# IFM_DuberFilter_ThroughHole_PCB_REV1.net
KiCad netlist of a schematic drawn in EAGLE
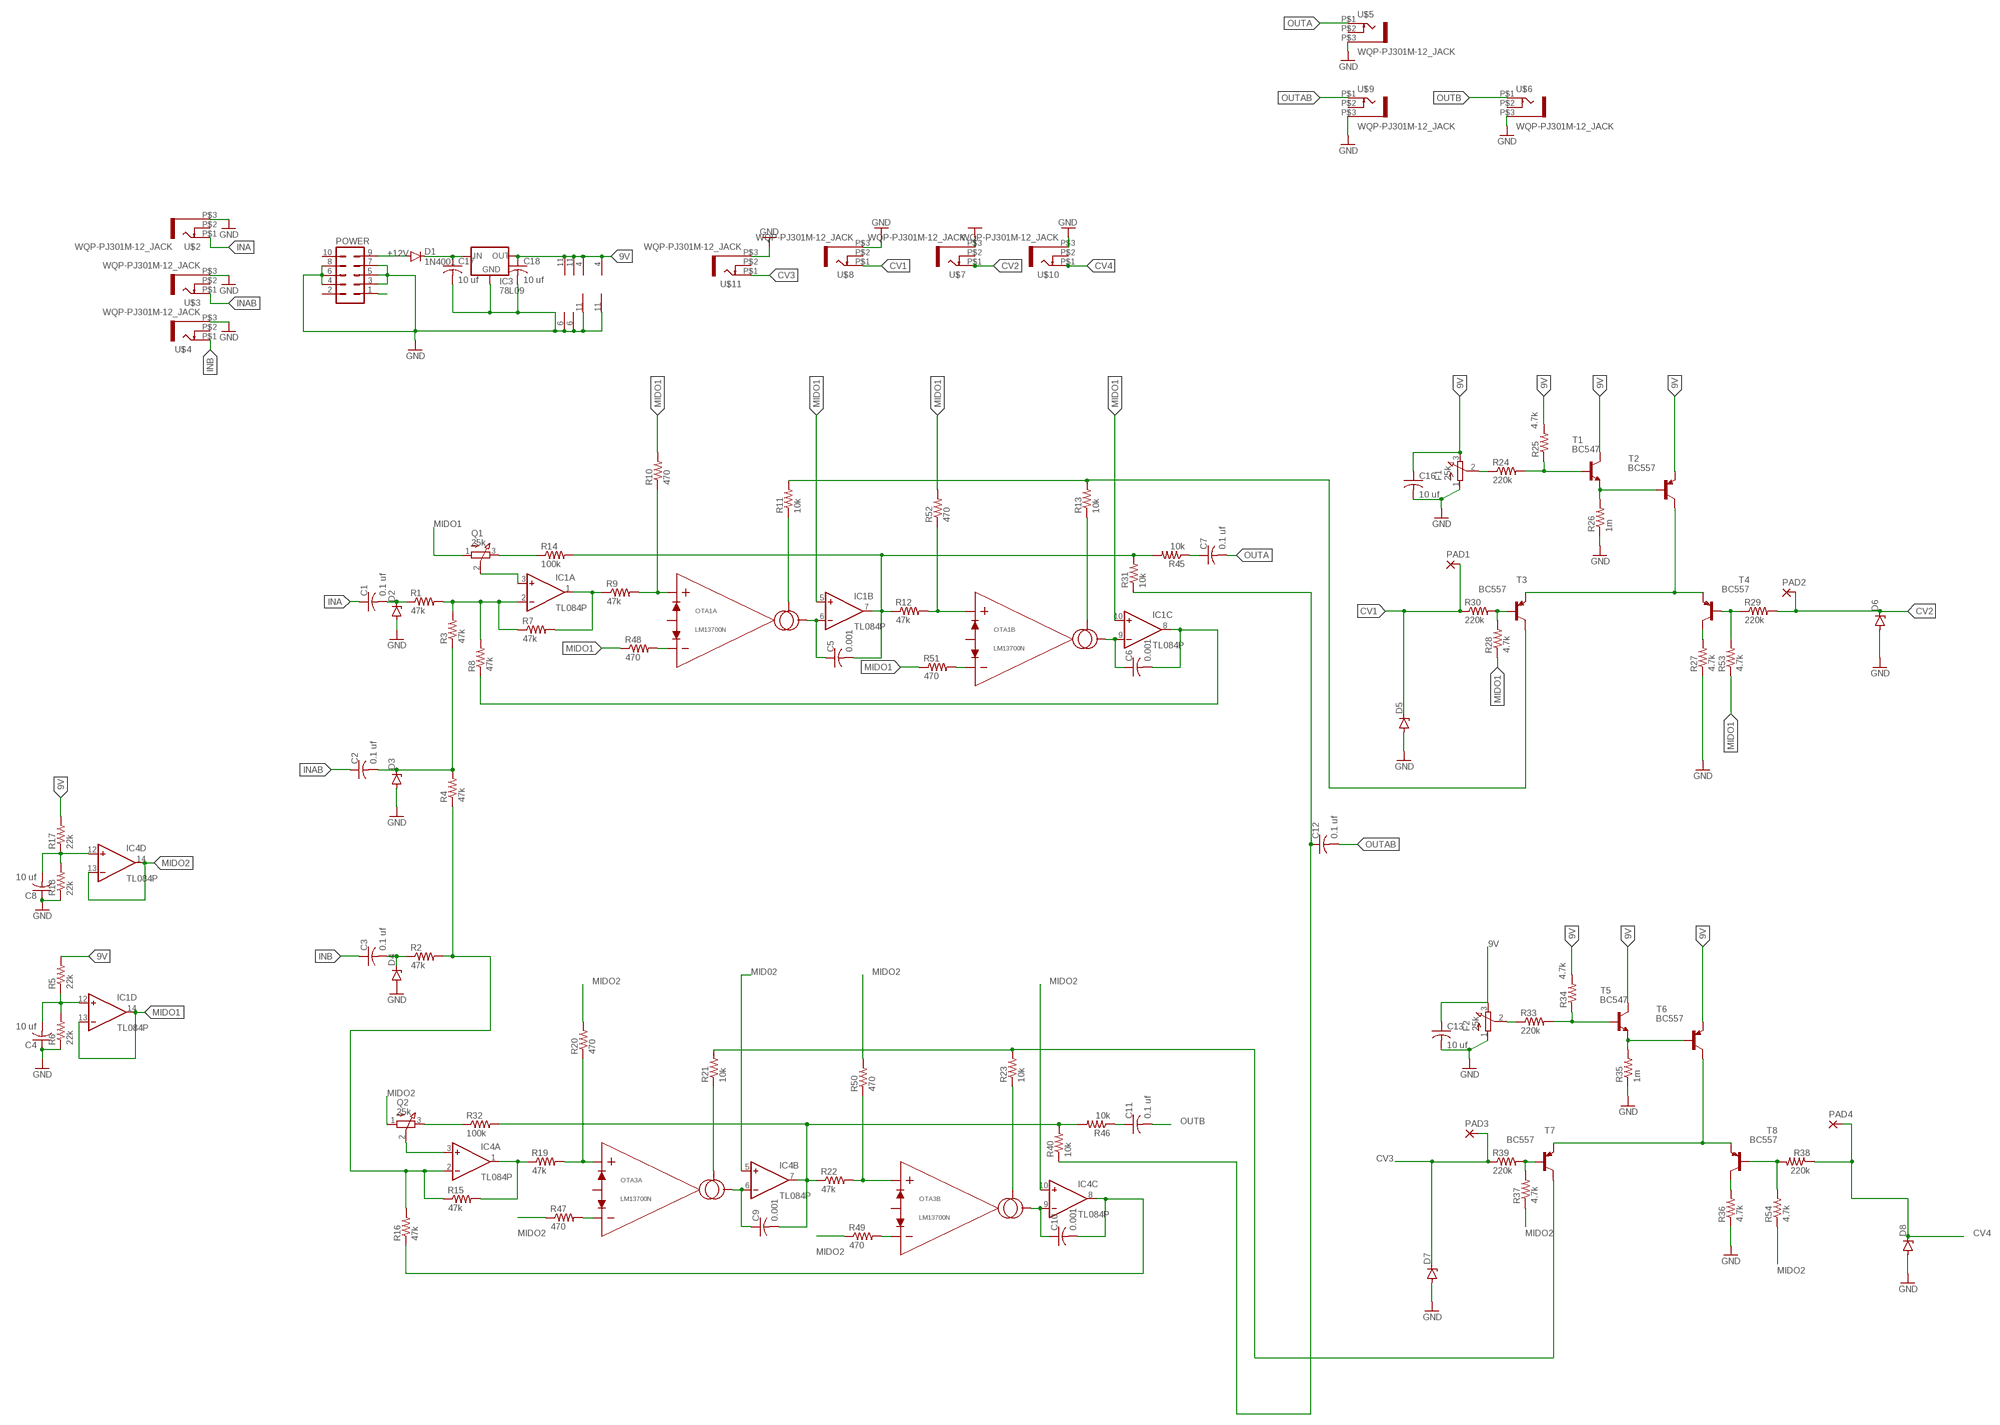
[diagram p0: schematic, sheet 1]

(export (version "E")
  (design (tool "Eeschema 10.0.6"))
  (components
    (comp (ref "C1")
      (value "0.1 uf")
      (footprint "eagle-import:C050-030X075")
      (libsource (lib "eagle-import") (part "C-US050-030X075"))
    )
    (comp (ref "C2")
      (value "0.1 uf")
      (footprint "eagle-import:C050-030X075")
      (libsource (lib "eagle-import") (part "C-US050-030X075"))
    )
    (comp (ref "C3")
      (value "0.1 uf")
      (footprint "eagle-import:C050-030X075")
      (libsource (lib "eagle-import") (part "C-US050-030X075"))
    )
    (comp (ref "C4")
      (value "10 uf")
      (footprint "eagle-import:C050-030X075")
      (libsource (lib "eagle-import") (part "C-US050-030X075"))
    )
    (comp (ref "C5")
      (value "0.001")
      (footprint "eagle-import:C050-030X075")
      (libsource (lib "eagle-import") (part "C-US050-030X075"))
    )
    (comp (ref "C6")
      (value "0.001")
      (footprint "eagle-import:C050-030X075")
      (libsource (lib "eagle-import") (part "C-US050-030X075"))
    )
    (comp (ref "C7")
      (value "0.1 uf")
      (footprint "eagle-import:C050-030X075")
      (libsource (lib "eagle-import") (part "C-US050-030X075"))
    )
    (comp (ref "C8")
      (value "10 uf")
      (footprint "eagle-import:C050-030X075")
      (libsource (lib "eagle-import") (part "C-US050-030X075"))
    )
    (comp (ref "C9")
      (value "0.001")
      (footprint "eagle-import:C050-030X075")
      (libsource (lib "eagle-import") (part "C-US050-030X075"))
    )
    (comp (ref "C10")
      (value "0.001")
      (footprint "eagle-import:C050-030X075")
      (libsource (lib "eagle-import") (part "C-US050-030X075"))
    )
    (comp (ref "C11")
      (value "0.1 uf")
      (footprint "eagle-import:C050-030X075")
      (libsource (lib "eagle-import") (part "C-US050-030X075"))
    )
    (comp (ref "C12")
      (value "0.1 uf")
      (footprint "eagle-import:C050-030X075")
      (libsource (lib "eagle-import") (part "C-US050-030X075"))
    )
    (comp (ref "C13")
      (value "10 uf")
      (footprint "eagle-import:C050-030X075")
      (libsource (lib "eagle-import") (part "C-US050-030X075"))
    )
    (comp (ref "C16")
      (value "10 uf")
      (footprint "eagle-import:C050-030X075")
      (libsource (lib "eagle-import") (part "C-US050-030X075"))
    )
    (comp (ref "C17")
      (value "10 uf")
      (footprint "eagle-import:C050-030X075")
      (libsource (lib "eagle-import") (part "C-US050-030X075"))
    )
    (comp (ref "C18")
      (value "10 uf")
      (footprint "eagle-import:C050-030X075")
      (libsource (lib "eagle-import") (part "C-US050-030X075"))
    )
    (comp (ref "D1")
      (value "1N4001")
      (footprint "eagle-import:DO41-10")
      (libsource (lib "eagle-import") (part "1N4004"))
    )
    (comp (ref "D2")
      (value "ZENER-DIODEDO34-7")
      (footprint "eagle-import:DO34Z7")
      (libsource (lib "eagle-import") (part "ZENER-DIODEDO34-7"))
    )
    (comp (ref "D3")
      (value "ZENER-DIODEDO34-7")
      (footprint "eagle-import:DO34Z7")
      (fields (field (name "SPICEPREFIX") "D"))
      (libsource (lib "eagle-import") (part "ZENER-DIODEDO34-7"))
    )
    (comp (ref "D4")
      (value "ZENER-DIODEDO34-7")
      (footprint "eagle-import:DO34Z7")
      (libsource (lib "eagle-import") (part "ZENER-DIODEDO34-7"))
    )
    (comp (ref "D5")
      (value "ZENER-DIODEDO34-7")
      (footprint "eagle-import:DO34Z7")
      (libsource (lib "eagle-import") (part "ZENER-DIODEDO34-7"))
    )
    (comp (ref "D6")
      (value "ZENER-DIODEDO34-7")
      (footprint "eagle-import:DO34Z7")
      (libsource (lib "eagle-import") (part "ZENER-DIODEDO34-7"))
    )
    (comp (ref "D7")
      (value "ZENER-DIODEDO34-7")
      (footprint "eagle-import:DO34Z7")
      (libsource (lib "eagle-import") (part "ZENER-DIODEDO34-7"))
    )
    (comp (ref "D8")
      (value "ZENER-DIODEDO34-7")
      (footprint "eagle-import:DO34Z7")
      (libsource (lib "eagle-import") (part "ZENER-DIODEDO34-7"))
    )
    (comp (ref "F1")
      (value "25k")
      (footprint "eagle-import:EVUFXL")
      (libsource (lib "eagle-import") (part "EVULF3"))
    )
    (comp (ref "F2")
      (value "25k")
      (footprint "eagle-import:EVUFXL")
      (libsource (lib "eagle-import") (part "EVULF3"))
    )
    (comp (ref "IC1")
      (value "TL084P")
      (footprint "eagle-import:DIL14")
      (libsource (lib "eagle-import") (part "TL084P"))
    )
    (comp (ref "IC3")
      (value "78L09")
      (footprint "eagle-import:78LXX")
      (libsource (lib "eagle-import") (part "78LXX"))
    )
    (comp (ref "IC4")
      (value "TL084P")
      (footprint "eagle-import:DIL14")
      (libsource (lib "eagle-import") (part "TL084P"))
    )
    (comp (ref "OTA1")
      (value "LM13700N")
      (footprint "eagle-import:DIP16")
      (libsource (lib "eagle-import") (part "LM13700N"))
    )
    (comp (ref "OTA3")
      (value "LM13700N")
      (footprint "eagle-import:DIP16")
      (libsource (lib "eagle-import") (part "LM13700N"))
    )
    (comp (ref "PAD1")
      (value "SMD2")
      (footprint "eagle-import:SMD1,27-2,54")
      (libsource (lib "eagle-import") (part "SMD2"))
    )
    (comp (ref "PAD2")
      (value "SMD2")
      (footprint "eagle-import:SMD1,27-2,54")
      (libsource (lib "eagle-import") (part "SMD2"))
    )
    (comp (ref "PAD3")
      (value "SMD2")
      (footprint "eagle-import:SMD1,27-2,54")
      (libsource (lib "eagle-import") (part "SMD2"))
    )
    (comp (ref "PAD4")
      (value "SMD2")
      (footprint "eagle-import:SMD1,27-2,54")
      (libsource (lib "eagle-import") (part "SMD2"))
    )
    (comp (ref "POWER")
      (value "10_PIN_HEADER")
      (footprint "eagle-import:MA05-2")
      (libsource (lib "eagle-import") (part "10_PIN_HEADER"))
    )
    (comp (ref "Q1")
      (value "25k")
      (footprint "eagle-import:EVUFXL")
      (libsource (lib "eagle-import") (part "EVULF3"))
    )
    (comp (ref "Q2")
      (value "25k")
      (footprint "eagle-import:EVUFXL")
      (libsource (lib "eagle-import") (part "EVULF3"))
    )
    (comp (ref "R1")
      (value "47k")
      (footprint "eagle-import:0204_7")
      (libsource (lib "eagle-import") (part "R-US_0204/7"))
    )
    (comp (ref "R2")
      (value "47k")
      (footprint "eagle-import:0204_7")
      (libsource (lib "eagle-import") (part "R-US_0204/7"))
    )
    (comp (ref "R3")
      (value "47k")
      (footprint "eagle-import:0204_7")
      (libsource (lib "eagle-import") (part "R-US_0204/7"))
    )
    (comp (ref "R4")
      (value "47k")
      (footprint "eagle-import:0204_7")
      (libsource (lib "eagle-import") (part "R-US_0204/7"))
    )
    (comp (ref "R5")
      (value "22k")
      (footprint "eagle-import:0204_7")
      (libsource (lib "eagle-import") (part "R-US_0204/7"))
    )
    (comp (ref "R6")
      (value "22k")
      (footprint "eagle-import:0204_7")
      (libsource (lib "eagle-import") (part "R-US_0204/7"))
    )
    (comp (ref "R7")
      (value "47k")
      (footprint "eagle-import:0204_7")
      (libsource (lib "eagle-import") (part "R-US_0204/7"))
    )
    (comp (ref "R8")
      (value "47k")
      (footprint "eagle-import:0204_7")
      (libsource (lib "eagle-import") (part "R-US_0204/7"))
    )
    (comp (ref "R9")
      (value "47k")
      (footprint "eagle-import:0204_7")
      (libsource (lib "eagle-import") (part "R-US_0204/7"))
    )
    (comp (ref "R10")
      (value "470")
      (footprint "eagle-import:0204_7")
      (libsource (lib "eagle-import") (part "R-US_0204/7"))
    )
    (comp (ref "R11")
      (value "10k")
      (footprint "eagle-import:0204_7")
      (libsource (lib "eagle-import") (part "R-US_0204/7"))
    )
    (comp (ref "R12")
      (value "47k")
      (footprint "eagle-import:0204_7")
      (libsource (lib "eagle-import") (part "R-US_0204/7"))
    )
    (comp (ref "R13")
      (value "10k")
      (footprint "eagle-import:0204_7")
      (libsource (lib "eagle-import") (part "R-US_0204/7"))
    )
    (comp (ref "R14")
      (value "100k")
      (footprint "eagle-import:0204_7")
      (libsource (lib "eagle-import") (part "R-US_0204/7"))
    )
    (comp (ref "R15")
      (value "47k")
      (footprint "eagle-import:0204_7")
      (libsource (lib "eagle-import") (part "R-US_0204/7"))
    )
    (comp (ref "R16")
      (value "47k")
      (footprint "eagle-import:0204_7")
      (libsource (lib "eagle-import") (part "R-US_0204/7"))
    )
    (comp (ref "R17")
      (value "22k")
      (footprint "eagle-import:0204_7")
      (libsource (lib "eagle-import") (part "R-US_0204/7"))
    )
    (comp (ref "R18")
      (value "22k")
      (footprint "eagle-import:0204_7")
      (libsource (lib "eagle-import") (part "R-US_0204/7"))
    )
    (comp (ref "R19")
      (value "47k")
      (footprint "eagle-import:0204_7")
      (libsource (lib "eagle-import") (part "R-US_0204/7"))
    )
    (comp (ref "R20")
      (value "470")
      (footprint "eagle-import:0204_7")
      (libsource (lib "eagle-import") (part "R-US_0204/7"))
    )
    (comp (ref "R21")
      (value "10k")
      (footprint "eagle-import:0204_7")
      (libsource (lib "eagle-import") (part "R-US_0204/7"))
    )
    (comp (ref "R22")
      (value "47k")
      (footprint "eagle-import:0204_7")
      (libsource (lib "eagle-import") (part "R-US_0204/7"))
    )
    (comp (ref "R23")
      (value "10k")
      (footprint "eagle-import:0204_7")
      (libsource (lib "eagle-import") (part "R-US_0204/7"))
    )
    (comp (ref "R24")
      (value "220k")
      (footprint "eagle-import:0204_7")
      (libsource (lib "eagle-import") (part "R-US_0204/7"))
    )
    (comp (ref "R25")
      (value "4.7k")
      (footprint "eagle-import:0204_7")
      (libsource (lib "eagle-import") (part "R-US_0204/7"))
    )
    (comp (ref "R26")
      (value "1m")
      (footprint "eagle-import:0204_7")
      (libsource (lib "eagle-import") (part "R-US_0204/7"))
    )
    (comp (ref "R27")
      (value "4.7k")
      (footprint "eagle-import:0204_7")
      (libsource (lib "eagle-import") (part "R-US_0204/7"))
    )
    (comp (ref "R28")
      (value "4.7k")
      (footprint "eagle-import:0204_7")
      (libsource (lib "eagle-import") (part "R-US_0204/7"))
    )
    (comp (ref "R29")
      (value "220k")
      (footprint "eagle-import:0204_7")
      (libsource (lib "eagle-import") (part "R-US_0204/7"))
    )
    (comp (ref "R30")
      (value "220k")
      (footprint "eagle-import:0204_7")
      (libsource (lib "eagle-import") (part "R-US_0204/7"))
    )
    (comp (ref "R31")
      (value "10k")
      (footprint "eagle-import:0204_7")
      (libsource (lib "eagle-import") (part "R-US_0204/7"))
    )
    (comp (ref "R32")
      (value "100k")
      (footprint "eagle-import:0204_7")
      (libsource (lib "eagle-import") (part "R-US_0204/7"))
    )
    (comp (ref "R33")
      (value "220k")
      (footprint "eagle-import:0204_7")
      (libsource (lib "eagle-import") (part "R-US_0204/7"))
    )
    (comp (ref "R34")
      (value "4.7k")
      (footprint "eagle-import:0204_7")
      (libsource (lib "eagle-import") (part "R-US_0204/7"))
    )
    (comp (ref "R35")
      (value "1m")
      (footprint "eagle-import:0204_7")
      (libsource (lib "eagle-import") (part "R-US_0204/7"))
    )
    (comp (ref "R36")
      (value "4.7k")
      (footprint "eagle-import:0204_7")
      (libsource (lib "eagle-import") (part "R-US_0204/7"))
    )
    (comp (ref "R37")
      (value "4.7k")
      (footprint "eagle-import:0204_7")
      (libsource (lib "eagle-import") (part "R-US_0204/7"))
    )
    (comp (ref "R38")
      (value "220k")
      (footprint "eagle-import:0204_7")
      (libsource (lib "eagle-import") (part "R-US_0204/7"))
    )
    (comp (ref "R39")
      (value "220k")
      (footprint "eagle-import:0204_7")
      (libsource (lib "eagle-import") (part "R-US_0204/7"))
    )
    (comp (ref "R40")
      (value "10k")
      (footprint "eagle-import:0204_7")
      (libsource (lib "eagle-import") (part "R-US_0204/7"))
    )
    (comp (ref "R45")
      (value "10k")
      (footprint "eagle-import:0204_7")
      (libsource (lib "eagle-import") (part "R-US_0204/7"))
    )
    (comp (ref "R46")
      (value "10k")
      (footprint "eagle-import:0204_7")
      (libsource (lib "eagle-import") (part "R-US_0204/7"))
    )
    (comp (ref "R47")
      (value "470")
      (footprint "eagle-import:0204_7")
      (libsource (lib "eagle-import") (part "R-US_0204/7"))
    )
    (comp (ref "R48")
      (value "470")
      (footprint "eagle-import:0204_7")
      (libsource (lib "eagle-import") (part "R-US_0204/7"))
    )
    (comp (ref "R49")
      (value "470")
      (footprint "eagle-import:0204_7")
      (libsource (lib "eagle-import") (part "R-US_0204/7"))
    )
    (comp (ref "R50")
      (value "470")
      (footprint "eagle-import:0204_7")
      (libsource (lib "eagle-import") (part "R-US_0204/7"))
    )
    (comp (ref "R51")
      (value "470")
      (footprint "eagle-import:0204_7")
      (libsource (lib "eagle-import") (part "R-US_0204/7"))
    )
    (comp (ref "R52")
      (value "470")
      (footprint "eagle-import:0204_7")
      (libsource (lib "eagle-import") (part "R-US_0204/7"))
    )
    (comp (ref "R53")
      (value "4.7k")
      (footprint "eagle-import:0204_7")
      (libsource (lib "eagle-import") (part "R-US_0204/7"))
    )
    (comp (ref "R54")
      (value "4.7k")
      (footprint "eagle-import:0204_7")
      (libsource (lib "eagle-import") (part "R-US_0204/7"))
    )
    (comp (ref "T1")
      (value "BC547")
      (footprint "eagle-import:TO92")
      (libsource (lib "eagle-import") (part "BC547"))
    )
    (comp (ref "T2")
      (value "BC557")
      (footprint "eagle-import:TO92-EBC")
      (libsource (lib "eagle-import") (part "-PNP-TO92-EBCBC557A"))
    )
    (comp (ref "T3")
      (value "BC557")
      (footprint "eagle-import:TO92-EBC")
      (libsource (lib "eagle-import") (part "-PNP-TO92-EBCBC557A"))
    )
    (comp (ref "T4")
      (value "BC557")
      (footprint "eagle-import:TO92-EBC")
      (libsource (lib "eagle-import") (part "-PNP-TO92-EBCBC557A"))
    )
    (comp (ref "T5")
      (value "BC547")
      (footprint "eagle-import:TO92")
      (libsource (lib "eagle-import") (part "BC547"))
    )
    (comp (ref "T6")
      (value "BC557")
      (footprint "eagle-import:TO92-EBC")
      (libsource (lib "eagle-import") (part "-PNP-TO92-EBCBC557A"))
    )
    (comp (ref "T7")
      (value "BC557")
      (footprint "eagle-import:TO92-EBC")
      (libsource (lib "eagle-import") (part "-PNP-TO92-EBCBC557A"))
    )
    (comp (ref "T8")
      (value "BC557")
      (footprint "eagle-import:TO92-EBC")
      (libsource (lib "eagle-import") (part "-PNP-TO92-EBCBC557A"))
    )
    (comp (ref "U$2")
      (value "WQP-PJ301M-12_JACK")
      (footprint "eagle-import:WQP-PJ301M-12_JACK")
      (libsource (lib "eagle-import") (part "WQP-PJ301M-12_JACK"))
    )
    (comp (ref "U$3")
      (value "WQP-PJ301M-12_JACK")
      (footprint "eagle-import:WQP-PJ301M-12_JACK")
      (libsource (lib "eagle-import") (part "WQP-PJ301M-12_JACK"))
    )
    (comp (ref "U$4")
      (value "WQP-PJ301M-12_JACK")
      (footprint "eagle-import:WQP-PJ301M-12_JACK")
      (libsource (lib "eagle-import") (part "WQP-PJ301M-12_JACK"))
    )
    (comp (ref "U$5")
      (value "WQP-PJ301M-12_JACK")
      (footprint "eagle-import:WQP-PJ301M-12_JACK")
      (libsource (lib "eagle-import") (part "WQP-PJ301M-12_JACK"))
    )
    (comp (ref "U$6")
      (value "WQP-PJ301M-12_JACK")
      (footprint "eagle-import:WQP-PJ301M-12_JACK")
      (libsource (lib "eagle-import") (part "WQP-PJ301M-12_JACK"))
    )
    (comp (ref "U$7")
      (value "WQP-PJ301M-12_JACK")
      (footprint "eagle-import:WQP-PJ301M-12_JACK")
      (libsource (lib "eagle-import") (part "WQP-PJ301M-12_JACK"))
    )
    (comp (ref "U$8")
      (value "WQP-PJ301M-12_JACK")
      (footprint "eagle-import:WQP-PJ301M-12_JACK")
      (libsource (lib "eagle-import") (part "WQP-PJ301M-12_JACK"))
    )
    (comp (ref "U$9")
      (value "WQP-PJ301M-12_JACK")
      (footprint "eagle-import:WQP-PJ301M-12_JACK")
      (libsource (lib "eagle-import") (part "WQP-PJ301M-12_JACK"))
    )
    (comp (ref "U$10")
      (value "WQP-PJ301M-12_JACK")
      (footprint "eagle-import:WQP-PJ301M-12_JACK")
      (libsource (lib "eagle-import") (part "WQP-PJ301M-12_JACK"))
    )
    (comp (ref "U$11")
      (value "WQP-PJ301M-12_JACK")
      (footprint "eagle-import:WQP-PJ301M-12_JACK")
      (libsource (lib "eagle-import") (part "WQP-PJ301M-12_JACK"))
    )
  )
  (nets
    (net (code "1") (name "/+12V") (class "Default")
      (node (ref "C17") (pin "1") (pinfunction "1_1") (pintype "passive"))
      (node (ref "D1") (pin "C") (pinfunction "C_C") (pintype "passive"))
      (node (ref "IC3") (pin "IN") (pinfunction "IN_IN") (pintype "input"))
    )
    (net (code "2") (name "/MID02") (class "Default")
      (node (ref "IC4") (pin "5") (pinfunction "+IN_5") (pintype "input"))
    )
    (net (code "3") (name "9V") (class "Default")
      (node (ref "C13") (pin "1") (pinfunction "1_1") (pintype "passive"))
      (node (ref "C16") (pin "1") (pinfunction "1_1") (pintype "passive"))
      (node (ref "C18") (pin "1") (pinfunction "1_1") (pintype "passive"))
      (node (ref "F1") (pin "3") (pinfunction "E_3") (pintype "passive"))
      (node (ref "F2") (pin "3") (pinfunction "E_3") (pintype "passive"))
      (node (ref "IC1") (pin "4") (pinfunction "V+_4") (pintype "power_in"))
      (node (ref "IC3") (pin "OUT") (pinfunction "OUT_OUT") (pintype "passive"))
      (node (ref "IC4") (pin "4") (pinfunction "V+_4") (pintype "power_in"))
      (node (ref "OTA1") (pin "11") (pinfunction "VCC_11") (pintype "power_in"))
      (node (ref "OTA3") (pin "11") (pinfunction "VCC_11") (pintype "power_in"))
      (node (ref "R17") (pin "2") (pinfunction "2_2") (pintype "passive"))
      (node (ref "R25") (pin "2") (pinfunction "2_2") (pintype "passive"))
      (node (ref "R34") (pin "2") (pinfunction "2_2") (pintype "passive"))
      (node (ref "R5") (pin "2") (pinfunction "2_2") (pintype "passive"))
      (node (ref "T1") (pin "3") (pinfunction "C_3") (pintype "passive"))
      (node (ref "T2") (pin "E") (pinfunction "E_E") (pintype "passive"))
      (node (ref "T5") (pin "3") (pinfunction "C_3") (pintype "passive"))
      (node (ref "T6") (pin "E") (pinfunction "E_E") (pintype "passive"))
    )
    (net (code "4") (name "CV1") (class "Default")
      (node (ref "D5") (pin "C") (pinfunction "C_C") (pintype "passive"))
      (node (ref "PAD1") (pin "1") (pinfunction "P_1") (pintype "passive"))
      (node (ref "R30") (pin "1") (pinfunction "1_1") (pintype "passive"))
      (node (ref "U$8") (pin "P$1") (pinfunction "2_P$1") (pintype "passive"))
    )
    (net (code "5") (name "CV2") (class "Default")
      (node (ref "D6") (pin "C") (pinfunction "C_C") (pintype "passive"))
      (node (ref "PAD2") (pin "1") (pinfunction "P_1") (pintype "passive"))
      (node (ref "R29") (pin "2") (pinfunction "2_2") (pintype "passive"))
      (node (ref "U$7") (pin "P$1") (pinfunction "2_P$1") (pintype "passive"))
    )
    (net (code "6") (name "CV3") (class "Default")
      (node (ref "D7") (pin "C") (pinfunction "C_C") (pintype "passive"))
      (node (ref "PAD3") (pin "1") (pinfunction "P_1") (pintype "passive"))
      (node (ref "R39") (pin "1") (pinfunction "1_1") (pintype "passive"))
      (node (ref "U$11") (pin "P$1") (pinfunction "2_P$1") (pintype "passive"))
    )
    (net (code "7") (name "CV4") (class "Default")
      (node (ref "D8") (pin "C") (pinfunction "C_C") (pintype "passive"))
      (node (ref "PAD4") (pin "1") (pinfunction "P_1") (pintype "passive"))
      (node (ref "R38") (pin "1") (pinfunction "1_1") (pintype "passive"))
      (node (ref "U$10") (pin "P$1") (pinfunction "2_P$1") (pintype "passive"))
    )
    (net (code "8") (name "GND") (class "Default")
      (node (ref "C13") (pin "2") (pinfunction "2_2") (pintype "passive"))
      (node (ref "C16") (pin "2") (pinfunction "2_2") (pintype "passive"))
      (node (ref "C17") (pin "2") (pinfunction "2_2") (pintype "passive"))
      (node (ref "C18") (pin "2") (pinfunction "2_2") (pintype "passive"))
      (node (ref "C4") (pin "1") (pinfunction "1_1") (pintype "passive"))
      (node (ref "C8") (pin "1") (pinfunction "1_1") (pintype "passive"))
      (node (ref "D2") (pin "A") (pinfunction "A_A") (pintype "passive"))
      (node (ref "D3") (pin "A") (pinfunction "A_A") (pintype "passive"))
      (node (ref "D4") (pin "A") (pinfunction "A_A") (pintype "passive"))
      (node (ref "D5") (pin "A") (pinfunction "A_A") (pintype "passive"))
      (node (ref "D6") (pin "A") (pinfunction "A_A") (pintype "passive"))
      (node (ref "D7") (pin "A") (pinfunction "A_A") (pintype "passive"))
      (node (ref "D8") (pin "A") (pinfunction "A_A") (pintype "passive"))
      (node (ref "F1") (pin "1") (pinfunction "A_1") (pintype "passive"))
      (node (ref "F2") (pin "1") (pinfunction "A_1") (pintype "passive"))
      (node (ref "IC1") (pin "11") (pinfunction "V-_11") (pintype "power_in"))
      (node (ref "IC3") (pin "GND") (pinfunction "GND_GND") (pintype "input"))
      (node (ref "IC4") (pin "11") (pinfunction "V-_11") (pintype "power_in"))
      (node (ref "OTA1") (pin "6") (pinfunction "VEE_6") (pintype "power_in"))
      (node (ref "OTA3") (pin "6") (pinfunction "VEE_6") (pintype "power_in"))
      (node (ref "POWER") (pin "3") (pinfunction "3_3") (pintype "passive"))
      (node (ref "POWER") (pin "4") (pinfunction "4_4") (pintype "passive"))
      (node (ref "POWER") (pin "5") (pinfunction "5_5") (pintype "passive"))
      (node (ref "POWER") (pin "6") (pinfunction "6_6") (pintype "passive"))
      (node (ref "POWER") (pin "7") (pinfunction "7_7") (pintype "passive"))
      (node (ref "POWER") (pin "8") (pinfunction "8_8") (pintype "passive"))
      (node (ref "R18") (pin "1") (pinfunction "1_1") (pintype "passive"))
      (node (ref "R26") (pin "1") (pinfunction "1_1") (pintype "passive"))
      (node (ref "R27") (pin "1") (pinfunction "1_1") (pintype "passive"))
      (node (ref "R35") (pin "1") (pinfunction "1_1") (pintype "passive"))
      (node (ref "R36") (pin "1") (pinfunction "1_1") (pintype "passive"))
      (node (ref "R6") (pin "1") (pinfunction "1_1") (pintype "passive"))
      (node (ref "U$10") (pin "P$3") (pinfunction "1_P$3") (pintype "passive"))
      (node (ref "U$11") (pin "P$3") (pinfunction "1_P$3") (pintype "passive"))
      (node (ref "U$2") (pin "P$3") (pinfunction "1_P$3") (pintype "passive"))
      (node (ref "U$3") (pin "P$3") (pinfunction "1_P$3") (pintype "passive"))
      (node (ref "U$4") (pin "P$3") (pinfunction "1_P$3") (pintype "passive"))
      (node (ref "U$5") (pin "P$3") (pinfunction "1_P$3") (pintype "passive"))
      (node (ref "U$6") (pin "P$3") (pinfunction "1_P$3") (pintype "passive"))
      (node (ref "U$7") (pin "P$3") (pinfunction "1_P$3") (pintype "passive"))
      (node (ref "U$8") (pin "P$3") (pinfunction "1_P$3") (pintype "passive"))
      (node (ref "U$9") (pin "P$3") (pinfunction "1_P$3") (pintype "passive"))
    )
    (net (code "9") (name "INA") (class "Default")
      (node (ref "C1") (pin "1") (pinfunction "1_1") (pintype "passive"))
      (node (ref "U$2") (pin "P$1") (pinfunction "2_P$1") (pintype "passive"))
    )
    (net (code "10") (name "INAB") (class "Default")
      (node (ref "C2") (pin "1") (pinfunction "1_1") (pintype "passive"))
      (node (ref "U$3") (pin "P$1") (pinfunction "2_P$1") (pintype "passive"))
    )
    (net (code "11") (name "INB") (class "Default")
      (node (ref "C3") (pin "1") (pinfunction "1_1") (pintype "passive"))
      (node (ref "U$4") (pin "P$1") (pinfunction "2_P$1") (pintype "passive"))
    )
    (net (code "12") (name "MIDO1") (class "Default")
      (node (ref "IC1") (pin "10") (pinfunction "+IN_10") (pintype "input"))
      (node (ref "IC1") (pin "13") (pinfunction "-IN_13") (pintype "input"))
      (node (ref "IC1") (pin "14") (pinfunction "OUT_14") (pintype "output"))
      (node (ref "IC1") (pin "5") (pinfunction "+IN_5") (pintype "input"))
      (node (ref "Q1") (pin "1") (pinfunction "A_1") (pintype "passive"))
      (node (ref "R10") (pin "2") (pinfunction "2_2") (pintype "passive"))
      (node (ref "R28") (pin "1") (pinfunction "1_1") (pintype "passive"))
      (node (ref "R48") (pin "1") (pinfunction "1_1") (pintype "passive"))
      (node (ref "R51") (pin "1") (pinfunction "1_1") (pintype "passive"))
      (node (ref "R52") (pin "2") (pinfunction "2_2") (pintype "passive"))
      (node (ref "R53") (pin "1") (pinfunction "1_1") (pintype "passive"))
    )
    (net (code "13") (name "MIDO2") (class "Default")
      (node (ref "IC4") (pin "10") (pinfunction "+IN_10") (pintype "input"))
      (node (ref "IC4") (pin "13") (pinfunction "-IN_13") (pintype "input"))
      (node (ref "IC4") (pin "14") (pinfunction "OUT_14") (pintype "output"))
      (node (ref "Q2") (pin "1") (pinfunction "A_1") (pintype "passive"))
      (node (ref "R20") (pin "2") (pinfunction "2_2") (pintype "passive"))
      (node (ref "R37") (pin "1") (pinfunction "1_1") (pintype "passive"))
      (node (ref "R47") (pin "1") (pinfunction "1_1") (pintype "passive"))
      (node (ref "R49") (pin "1") (pinfunction "1_1") (pintype "passive"))
      (node (ref "R50") (pin "2") (pinfunction "2_2") (pintype "passive"))
      (node (ref "R54") (pin "1") (pinfunction "1_1") (pintype "passive"))
    )
    (net (code "14") (name "Net-(C1-Pad2)") (class "Default")
      (node (ref "C1") (pin "2") (pinfunction "2_2") (pintype "passive"))
      (node (ref "D2") (pin "C") (pinfunction "C_C") (pintype "passive"))
      (node (ref "R1") (pin "1") (pinfunction "1_1") (pintype "passive"))
    )
    (net (code "15") (name "Net-(C2-Pad2)") (class "Default")
      (node (ref "C2") (pin "2") (pinfunction "2_2") (pintype "passive"))
      (node (ref "D3") (pin "C") (pinfunction "C_C") (pintype "passive"))
      (node (ref "R3") (pin "1") (pinfunction "1_1") (pintype "passive"))
      (node (ref "R4") (pin "2") (pinfunction "2_2") (pintype "passive"))
    )
    (net (code "16") (name "Net-(C3-Pad2)") (class "Default")
      (node (ref "C3") (pin "2") (pinfunction "2_2") (pintype "passive"))
      (node (ref "D4") (pin "C") (pinfunction "C_C") (pintype "passive"))
      (node (ref "R2") (pin "1") (pinfunction "1_1") (pintype "passive"))
    )
    (net (code "17") (name "Net-(C7-Pad1)") (class "Default")
      (node (ref "C7") (pin "1") (pinfunction "1_1") (pintype "passive"))
      (node (ref "R45") (pin "1") (pinfunction "1_1") (pintype "passive"))
    )
    (net (code "18") (name "Net-(C11-Pad1)") (class "Default")
      (node (ref "C11") (pin "1") (pinfunction "1_1") (pintype "passive"))
      (node (ref "R46") (pin "1") (pinfunction "1_1") (pintype "passive"))
    )
    (net (code "19") (name "Net-(C12-Pad1)") (class "Default")
      (node (ref "C12") (pin "1") (pinfunction "1_1") (pintype "passive"))
      (node (ref "R31") (pin "1") (pinfunction "1_1") (pintype "passive"))
      (node (ref "R40") (pin "1") (pinfunction "1_1") (pintype "passive"))
    )
    (net (code "20") (name "Net-(D1-PadA)") (class "Default")
      (node (ref "D1") (pin "A") (pinfunction "A_A") (pintype "passive"))
      (node (ref "POWER") (pin "9") (pinfunction "9_9") (pintype "passive"))
    )
    (net (code "21") (name "Net-(F1-S)") (class "Default")
      (node (ref "F1") (pin "2") (pinfunction "S_2") (pintype "passive"))
      (node (ref "R24") (pin "1") (pinfunction "1_1") (pintype "passive"))
    )
    (net (code "22") (name "Net-(F2-S)") (class "Default")
      (node (ref "F2") (pin "2") (pinfunction "S_2") (pintype "passive"))
      (node (ref "R33") (pin "1") (pinfunction "1_1") (pintype "passive"))
    )
    (net (code "23") (name "Net-(IC1A-+IN)") (class "Default")
      (node (ref "IC1") (pin "3") (pinfunction "+IN_3") (pintype "input"))
      (node (ref "Q1") (pin "2") (pinfunction "S_2") (pintype "passive"))
    )
    (net (code "24") (name "Net-(IC1A--IN)") (class "Default")
      (node (ref "IC1") (pin "2") (pinfunction "-IN_2") (pintype "input"))
      (node (ref "R1") (pin "2") (pinfunction "2_2") (pintype "passive"))
      (node (ref "R3") (pin "2") (pinfunction "2_2") (pintype "passive"))
      (node (ref "R7") (pin "1") (pinfunction "1_1") (pintype "passive"))
      (node (ref "R8") (pin "2") (pinfunction "2_2") (pintype "passive"))
    )
    (net (code "25") (name "Net-(IC1A-OUT)") (class "Default")
      (node (ref "IC1") (pin "1") (pinfunction "OUT_1") (pintype "output"))
      (node (ref "R7") (pin "2") (pinfunction "2_2") (pintype "passive"))
      (node (ref "R9") (pin "1") (pinfunction "1_1") (pintype "passive"))
    )
    (net (code "26") (name "Net-(IC1B--IN)") (class "Default")
      (node (ref "C5") (pin "1") (pinfunction "1_1") (pintype "passive"))
      (node (ref "IC1") (pin "6") (pinfunction "-IN_6") (pintype "input"))
      (node (ref "OTA1") (pin "5") (pinfunction "IOUT_5") (pintype "output"))
    )
    (net (code "27") (name "Net-(IC1B-OUT)") (class "Default")
      (node (ref "C5") (pin "2") (pinfunction "2_2") (pintype "passive"))
      (node (ref "IC1") (pin "7") (pinfunction "OUT_7") (pintype "output"))
      (node (ref "R12") (pin "1") (pinfunction "1_1") (pintype "passive"))
      (node (ref "R14") (pin "2") (pinfunction "2_2") (pintype "passive"))
      (node (ref "R31") (pin "2") (pinfunction "2_2") (pintype "passive"))
      (node (ref "R45") (pin "2") (pinfunction "2_2") (pintype "passive"))
    )
    (net (code "28") (name "Net-(IC1C--IN)") (class "Default")
      (node (ref "C6") (pin "1") (pinfunction "1_1") (pintype "passive"))
      (node (ref "IC1") (pin "9") (pinfunction "-IN_9") (pintype "input"))
      (node (ref "OTA1") (pin "12") (pinfunction "IOUT_12") (pintype "output"))
    )
    (net (code "29") (name "Net-(IC1C-OUT)") (class "Default")
      (node (ref "C6") (pin "2") (pinfunction "2_2") (pintype "passive"))
      (node (ref "IC1") (pin "8") (pinfunction "OUT_8") (pintype "output"))
      (node (ref "R8") (pin "1") (pinfunction "1_1") (pintype "passive"))
    )
    (net (code "30") (name "Net-(IC1D-+IN)") (class "Default")
      (node (ref "C4") (pin "2") (pinfunction "2_2") (pintype "passive"))
      (node (ref "IC1") (pin "12") (pinfunction "+IN_12") (pintype "input"))
      (node (ref "R5") (pin "1") (pinfunction "1_1") (pintype "passive"))
      (node (ref "R6") (pin "2") (pinfunction "2_2") (pintype "passive"))
    )
    (net (code "31") (name "Net-(IC4A-+IN)") (class "Default")
      (node (ref "IC4") (pin "3") (pinfunction "+IN_3") (pintype "input"))
      (node (ref "Q2") (pin "2") (pinfunction "S_2") (pintype "passive"))
    )
    (net (code "32") (name "Net-(IC4A--IN)") (class "Default")
      (node (ref "IC4") (pin "2") (pinfunction "-IN_2") (pintype "input"))
      (node (ref "R15") (pin "1") (pinfunction "1_1") (pintype "passive"))
      (node (ref "R16") (pin "2") (pinfunction "2_2") (pintype "passive"))
      (node (ref "R2") (pin "2") (pinfunction "2_2") (pintype "passive"))
      (node (ref "R4") (pin "1") (pinfunction "1_1") (pintype "passive"))
    )
    (net (code "33") (name "Net-(IC4A-OUT)") (class "Default")
      (node (ref "IC4") (pin "1") (pinfunction "OUT_1") (pintype "output"))
      (node (ref "R15") (pin "2") (pinfunction "2_2") (pintype "passive"))
      (node (ref "R19") (pin "1") (pinfunction "1_1") (pintype "passive"))
    )
    (net (code "34") (name "Net-(IC4B--IN)") (class "Default")
      (node (ref "C9") (pin "1") (pinfunction "1_1") (pintype "passive"))
      (node (ref "IC4") (pin "6") (pinfunction "-IN_6") (pintype "input"))
      (node (ref "OTA3") (pin "5") (pinfunction "IOUT_5") (pintype "output"))
    )
    (net (code "35") (name "Net-(IC4B-OUT)") (class "Default")
      (node (ref "C9") (pin "2") (pinfunction "2_2") (pintype "passive"))
      (node (ref "IC4") (pin "7") (pinfunction "OUT_7") (pintype "output"))
      (node (ref "R22") (pin "1") (pinfunction "1_1") (pintype "passive"))
      (node (ref "R32") (pin "2") (pinfunction "2_2") (pintype "passive"))
      (node (ref "R40") (pin "2") (pinfunction "2_2") (pintype "passive"))
      (node (ref "R46") (pin "2") (pinfunction "2_2") (pintype "passive"))
    )
    (net (code "36") (name "Net-(IC4C--IN)") (class "Default")
      (node (ref "C10") (pin "1") (pinfunction "1_1") (pintype "passive"))
      (node (ref "IC4") (pin "9") (pinfunction "-IN_9") (pintype "input"))
      (node (ref "OTA3") (pin "12") (pinfunction "IOUT_12") (pintype "output"))
    )
    (net (code "37") (name "Net-(IC4C-OUT)") (class "Default")
      (node (ref "C10") (pin "2") (pinfunction "2_2") (pintype "passive"))
      (node (ref "IC4") (pin "8") (pinfunction "OUT_8") (pintype "output"))
      (node (ref "R16") (pin "1") (pinfunction "1_1") (pintype "passive"))
    )
    (net (code "38") (name "Net-(IC4D-+IN)") (class "Default")
      (node (ref "C8") (pin "2") (pinfunction "2_2") (pintype "passive"))
      (node (ref "IC4") (pin "12") (pinfunction "+IN_12") (pintype "input"))
      (node (ref "R17") (pin "1") (pinfunction "1_1") (pintype "passive"))
      (node (ref "R18") (pin "2") (pinfunction "2_2") (pintype "passive"))
    )
    (net (code "39") (name "Net-(OTA1A-IABC)") (class "Default")
      (node (ref "OTA1") (pin "1") (pinfunction "IABC_1") (pintype "input"))
      (node (ref "R11") (pin "1") (pinfunction "1_1") (pintype "passive"))
    )
    (net (code "40") (name "Net-(OTA1A-IN+)") (class "Default")
      (node (ref "OTA1") (pin "3") (pinfunction "IN+_3") (pintype "input"))
      (node (ref "R10") (pin "1") (pinfunction "1_1") (pintype "passive"))
      (node (ref "R9") (pin "2") (pinfunction "2_2") (pintype "passive"))
    )
    (net (code "41") (name "Net-(OTA1A-IN-)") (class "Default")
      (node (ref "OTA1") (pin "4") (pinfunction "IN-_4") (pintype "input"))
      (node (ref "R48") (pin "2") (pinfunction "2_2") (pintype "passive"))
    )
    (net (code "42") (name "Net-(OTA1B-IABC)") (class "Default")
      (node (ref "OTA1") (pin "16") (pinfunction "IABC_16") (pintype "input"))
      (node (ref "R13") (pin "1") (pinfunction "1_1") (pintype "passive"))
    )
    (net (code "43") (name "Net-(OTA1B-IN+)") (class "Default")
      (node (ref "OTA1") (pin "14") (pinfunction "IN+_14") (pintype "input"))
      (node (ref "R12") (pin "2") (pinfunction "2_2") (pintype "passive"))
      (node (ref "R52") (pin "1") (pinfunction "1_1") (pintype "passive"))
    )
    (net (code "44") (name "Net-(OTA1B-IN-)") (class "Default")
      (node (ref "OTA1") (pin "13") (pinfunction "IN-_13") (pintype "input"))
      (node (ref "R51") (pin "2") (pinfunction "2_2") (pintype "passive"))
    )
    (net (code "45") (name "Net-(OTA3A-IABC)") (class "Default")
      (node (ref "OTA3") (pin "1") (pinfunction "IABC_1") (pintype "input"))
      (node (ref "R21") (pin "1") (pinfunction "1_1") (pintype "passive"))
    )
    (net (code "46") (name "Net-(OTA3A-IN+)") (class "Default")
      (node (ref "OTA3") (pin "3") (pinfunction "IN+_3") (pintype "input"))
      (node (ref "R19") (pin "2") (pinfunction "2_2") (pintype "passive"))
      (node (ref "R20") (pin "1") (pinfunction "1_1") (pintype "passive"))
    )
    (net (code "47") (name "Net-(OTA3A-IN-)") (class "Default")
      (node (ref "OTA3") (pin "4") (pinfunction "IN-_4") (pintype "input"))
      (node (ref "R47") (pin "2") (pinfunction "2_2") (pintype "passive"))
    )
    (net (code "48") (name "Net-(OTA3B-IABC)") (class "Default")
      (node (ref "OTA3") (pin "16") (pinfunction "IABC_16") (pintype "input"))
      (node (ref "R23") (pin "1") (pinfunction "1_1") (pintype "passive"))
    )
    (net (code "49") (name "Net-(OTA3B-IN+)") (class "Default")
      (node (ref "OTA3") (pin "14") (pinfunction "IN+_14") (pintype "input"))
      (node (ref "R22") (pin "2") (pinfunction "2_2") (pintype "passive"))
      (node (ref "R50") (pin "1") (pinfunction "1_1") (pintype "passive"))
    )
    (net (code "50") (name "Net-(OTA3B-IN-)") (class "Default")
      (node (ref "OTA3") (pin "13") (pinfunction "IN-_13") (pintype "input"))
      (node (ref "R49") (pin "2") (pinfunction "2_2") (pintype "passive"))
    )
    (net (code "51") (name "Net-(Q1-E)") (class "Default")
      (node (ref "Q1") (pin "3") (pinfunction "E_3") (pintype "passive"))
      (node (ref "R14") (pin "1") (pinfunction "1_1") (pintype "passive"))
    )
    (net (code "52") (name "Net-(Q2-E)") (class "Default")
      (node (ref "Q2") (pin "3") (pinfunction "E_3") (pintype "passive"))
      (node (ref "R32") (pin "1") (pinfunction "1_1") (pintype "passive"))
    )
    (net (code "53") (name "Net-(R11-Pad2)") (class "Default")
      (node (ref "R11") (pin "2") (pinfunction "2_2") (pintype "passive"))
      (node (ref "R13") (pin "2") (pinfunction "2_2") (pintype "passive"))
      (node (ref "T3") (pin "C") (pinfunction "C_C") (pintype "passive"))
    )
    (net (code "54") (name "Net-(R21-Pad2)") (class "Default")
      (node (ref "R21") (pin "2") (pinfunction "2_2") (pintype "passive"))
      (node (ref "R23") (pin "2") (pinfunction "2_2") (pintype "passive"))
      (node (ref "T7") (pin "C") (pinfunction "C_C") (pintype "passive"))
    )
    (net (code "55") (name "Net-(R27-Pad2)") (class "Default")
      (node (ref "R27") (pin "2") (pinfunction "2_2") (pintype "passive"))
      (node (ref "T4") (pin "C") (pinfunction "C_C") (pintype "passive"))
    )
    (net (code "56") (name "Net-(R28-Pad2)") (class "Default")
      (node (ref "R28") (pin "2") (pinfunction "2_2") (pintype "passive"))
      (node (ref "R30") (pin "2") (pinfunction "2_2") (pintype "passive"))
      (node (ref "T3") (pin "B") (pinfunction "B_B") (pintype "passive"))
    )
    (net (code "57") (name "Net-(R29-Pad1)") (class "Default")
      (node (ref "R29") (pin "1") (pinfunction "1_1") (pintype "passive"))
      (node (ref "R53") (pin "2") (pinfunction "2_2") (pintype "passive"))
      (node (ref "T4") (pin "B") (pinfunction "B_B") (pintype "passive"))
    )
    (net (code "58") (name "Net-(R36-Pad2)") (class "Default")
      (node (ref "R36") (pin "2") (pinfunction "2_2") (pintype "passive"))
      (node (ref "T8") (pin "C") (pinfunction "C_C") (pintype "passive"))
    )
    (net (code "59") (name "Net-(R37-Pad2)") (class "Default")
      (node (ref "R37") (pin "2") (pinfunction "2_2") (pintype "passive"))
      (node (ref "R39") (pin "2") (pinfunction "2_2") (pintype "passive"))
      (node (ref "T7") (pin "B") (pinfunction "B_B") (pintype "passive"))
    )
    (net (code "60") (name "Net-(R38-Pad2)") (class "Default")
      (node (ref "R38") (pin "2") (pinfunction "2_2") (pintype "passive"))
      (node (ref "R54") (pin "2") (pinfunction "2_2") (pintype "passive"))
      (node (ref "T8") (pin "B") (pinfunction "B_B") (pintype "passive"))
    )
    (net (code "61") (name "Net-(T1-B)") (class "Default")
      (node (ref "R24") (pin "2") (pinfunction "2_2") (pintype "passive"))
      (node (ref "R25") (pin "1") (pinfunction "1_1") (pintype "passive"))
      (node (ref "T1") (pin "2") (pinfunction "B_2") (pintype "passive"))
    )
    (net (code "62") (name "Net-(T1-E)") (class "Default")
      (node (ref "R26") (pin "2") (pinfunction "2_2") (pintype "passive"))
      (node (ref "T1") (pin "1") (pinfunction "E_1") (pintype "passive"))
      (node (ref "T2") (pin "B") (pinfunction "B_B") (pintype "passive"))
    )
    (net (code "63") (name "Net-(T2-PadC)") (class "Default")
      (node (ref "T2") (pin "C") (pinfunction "C_C") (pintype "passive"))
      (node (ref "T3") (pin "E") (pinfunction "E_E") (pintype "passive"))
      (node (ref "T4") (pin "E") (pinfunction "E_E") (pintype "passive"))
    )
    (net (code "64") (name "Net-(T5-B)") (class "Default")
      (node (ref "R33") (pin "2") (pinfunction "2_2") (pintype "passive"))
      (node (ref "R34") (pin "1") (pinfunction "1_1") (pintype "passive"))
      (node (ref "T5") (pin "2") (pinfunction "B_2") (pintype "passive"))
    )
    (net (code "65") (name "Net-(T5-E)") (class "Default")
      (node (ref "R35") (pin "2") (pinfunction "2_2") (pintype "passive"))
      (node (ref "T5") (pin "1") (pinfunction "E_1") (pintype "passive"))
      (node (ref "T6") (pin "B") (pinfunction "B_B") (pintype "passive"))
    )
    (net (code "66") (name "Net-(T6-PadC)") (class "Default")
      (node (ref "T6") (pin "C") (pinfunction "C_C") (pintype "passive"))
      (node (ref "T7") (pin "E") (pinfunction "E_E") (pintype "passive"))
      (node (ref "T8") (pin "E") (pinfunction "E_E") (pintype "passive"))
    )
    (net (code "67") (name "OUTA") (class "Default")
      (node (ref "C7") (pin "2") (pinfunction "2_2") (pintype "passive"))
      (node (ref "U$5") (pin "P$1") (pinfunction "2_P$1") (pintype "passive"))
    )
    (net (code "68") (name "OUTAB") (class "Default")
      (node (ref "C12") (pin "2") (pinfunction "2_2") (pintype "passive"))
      (node (ref "U$9") (pin "P$1") (pinfunction "2_P$1") (pintype "passive"))
    )
    (net (code "69") (name "OUTB") (class "Default")
      (node (ref "C11") (pin "2") (pinfunction "2_2") (pintype "passive"))
      (node (ref "U$6") (pin "P$1") (pinfunction "2_P$1") (pintype "passive"))
    )
    (net (code "70") (name "unconnected-(OTA1A-BIAS-Pad2)") (class "Default")
      (node (ref "OTA1") (pin "2") (pinfunction "BIAS_2") (pintype "input"))
    )
    (net (code "71") (name "unconnected-(OTA1B-BIAS-Pad15)") (class "Default")
      (node (ref "OTA1") (pin "15") (pinfunction "BIAS_15") (pintype "input"))
    )
    (net (code "72") (name "unconnected-(OTA3A-BIAS-Pad2)") (class "Default")
      (node (ref "OTA3") (pin "2") (pinfunction "BIAS_2") (pintype "input"))
    )
    (net (code "73") (name "unconnected-(OTA3B-BIAS-Pad15)") (class "Default")
      (node (ref "OTA3") (pin "15") (pinfunction "BIAS_15") (pintype "input"))
    )
    (net (code "74") (name "unconnected-(POWER-Pad1)") (class "Default")
      (node (ref "POWER") (pin "1") (pinfunction "1_1") (pintype "passive"))
    )
    (net (code "75") (name "unconnected-(POWER-Pad2)") (class "Default")
      (node (ref "POWER") (pin "2") (pinfunction "2_2") (pintype "passive"))
    )
    (net (code "76") (name "unconnected-(POWER-Pad10)") (class "Default")
      (node (ref "POWER") (pin "10") (pinfunction "10_10") (pintype "passive"))
    )
    (net (code "77") (name "unconnected-(U$2-3-PadP$2)") (class "Default")
      (node (ref "U$2") (pin "P$2") (pinfunction "3_P$2") (pintype "passive"))
    )
    (net (code "78") (name "unconnected-(U$3-3-PadP$2)") (class "Default")
      (node (ref "U$3") (pin "P$2") (pinfunction "3_P$2") (pintype "passive"))
    )
    (net (code "79") (name "unconnected-(U$4-3-PadP$2)") (class "Default")
      (node (ref "U$4") (pin "P$2") (pinfunction "3_P$2") (pintype "passive"))
    )
    (net (code "80") (name "unconnected-(U$5-3-PadP$2)") (class "Default")
      (node (ref "U$5") (pin "P$2") (pinfunction "3_P$2") (pintype "passive"))
    )
    (net (code "81") (name "unconnected-(U$6-3-PadP$2)") (class "Default")
      (node (ref "U$6") (pin "P$2") (pinfunction "3_P$2") (pintype "passive"))
    )
    (net (code "82") (name "unconnected-(U$7-3-PadP$2)") (class "Default")
      (node (ref "U$7") (pin "P$2") (pinfunction "3_P$2") (pintype "passive"))
    )
    (net (code "83") (name "unconnected-(U$8-3-PadP$2)") (class "Default")
      (node (ref "U$8") (pin "P$2") (pinfunction "3_P$2") (pintype "passive"))
    )
    (net (code "84") (name "unconnected-(U$9-3-PadP$2)") (class "Default")
      (node (ref "U$9") (pin "P$2") (pinfunction "3_P$2") (pintype "passive"))
    )
    (net (code "85") (name "unconnected-(U$10-3-PadP$2)") (class "Default")
      (node (ref "U$10") (pin "P$2") (pinfunction "3_P$2") (pintype "passive"))
    )
    (net (code "86") (name "unconnected-(U$11-3-PadP$2)") (class "Default")
      (node (ref "U$11") (pin "P$2") (pinfunction "3_P$2") (pintype "passive"))
    )
  )
)
